# vending_machine_V1_0.net
KiCad netlist of a schematic drawn in Altium Designer
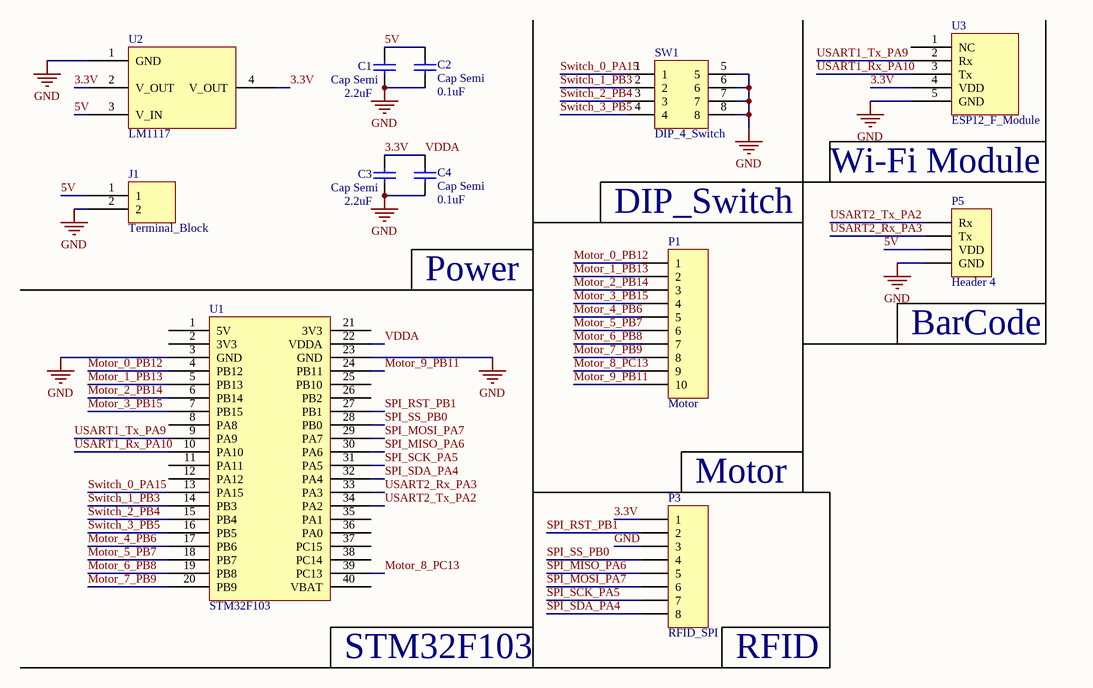
[diagram p0: vending_machine_V1.0.SchDoc]

(export (version "E")
  (design (tool "Eeschema 10.0.6"))
  (components
    (comp (ref "C1")
      (value "Cap Semi")
      (footprint "1608[0603]")
      (description "Capacitor (Semiconductor SIM Model)")
      (fields (field (name "ALTIUM_VALUE") "2.2uF") (field (name "PUBLISHER") "Altium Limited"))
      (libsource (lib "Miscellaneous Devices") (part "Cap Semi"))
    )
    (comp (ref "C2")
      (value "Cap Semi")
      (footprint "1608[0603]")
      (description "Capacitor (Semiconductor SIM Model)")
      (fields (field (name "ALTIUM_VALUE") "0.1uF") (field (name "PUBLISHER") "Altium Limited"))
      (libsource (lib "Miscellaneous Devices") (part "Cap Semi"))
    )
    (comp (ref "C3")
      (value "Cap Semi")
      (footprint "1608[0603]")
      (description "Capacitor (Semiconductor SIM Model)")
      (fields (field (name "ALTIUM_VALUE") "2.2uF") (field (name "PUBLISHER") "Altium Limited"))
      (libsource (lib "Miscellaneous Devices") (part "Cap Semi"))
    )
    (comp (ref "C4")
      (value "Cap Semi")
      (footprint "1608[0603]")
      (description "Capacitor (Semiconductor SIM Model)")
      (fields (field (name "ALTIUM_VALUE") "0.1uF") (field (name "PUBLISHER") "Altium Limited"))
      (libsource (lib "Miscellaneous Devices") (part "Cap Semi"))
    )
    (comp (ref "J1")
      (value "Terminal_Block")
      (footprint "terminal block")
      (libsource (lib "Lab_share") (part "Terminal Block"))
    )
    (comp (ref "P1")
      (value "Motor")
      (footprint "HDR1X10")
      (description "Header, 10-Pin")
      (fields (field (name "PUBLISHER") "Altium Limited"))
      (libsource (lib "Miscellaneous Connectors") (part "Header 10"))
    )
    (comp (ref "P3")
      (value "RFID_SPI")
      (footprint "HDR1X8")
      (description "Header, 8-Pin")
      (fields (field (name "PUBLISHER") "Altium Limited"))
      (libsource (lib "Miscellaneous Connectors") (part "Header 8"))
    )
    (comp (ref "P5")
      (value "Header 4")
      (footprint "HDR1X4")
      (description "Header, 4-Pin")
      (fields (field (name "PUBLISHER") "Altium Limited"))
      (libsource (lib "Miscellaneous Connectors") (part "Header 4"))
    )
    (comp (ref "SW1")
      (value "DIP_4_Switch")
      (footprint "Switch_4")
      (libsource (lib "Lab_share") (part "Switch_4"))
    )
    (comp (ref "U1")
      (value "STM32F103")
      (footprint "STM32F103")
      (libsource (lib "Lab_share") (part "STM32F103"))
    )
    (comp (ref "U2")
      (value "LM1117")
      (footprint "LM1117 - duplicate")
      (libsource (lib "Lab_share") (part "LM1117"))
    )
    (comp (ref "U3")
      (value "ESP12_F_Module")
      (footprint "ESP12_F_Holtek")
      (libsource (lib "Lab_share") (part "ESP12_F_Holtek"))
    )
  )
  (nets
    (net (code "1") (name "/3.3V") (class "Default")
      (node (ref "C3") (pin "2") (pinfunction "2_2") (pintype "passive"))
      (node (ref "C4") (pin "2") (pinfunction "2_2") (pintype "passive"))
      (node (ref "P3") (pin "1") (pinfunction "1_1") (pintype "passive"))
      (node (ref "U1") (pin "22") (pinfunction "VDDA_22") (pintype "passive"))
      (node (ref "U2") (pin "2") (pinfunction "V_OUT_2") (pintype "passive"))
      (node (ref "U2") (pin "4") (pinfunction "V_OUT_4") (pintype "passive"))
      (node (ref "U3") (pin "4") (pinfunction "VDD_4") (pintype "passive"))
    )
    (net (code "2") (name "/5V") (class "Default")
      (node (ref "C1") (pin "2") (pinfunction "2_2") (pintype "passive"))
      (node (ref "C2") (pin "2") (pinfunction "2_2") (pintype "passive"))
      (node (ref "J1") (pin "1") (pinfunction "1_1") (pintype "passive"))
      (node (ref "P5") (pin "3") (pinfunction "VDD_3") (pintype "passive"))
      (node (ref "U2") (pin "3") (pinfunction "V_IN_3") (pintype "passive"))
    )
    (net (code "3") (name "/Motor_0_PB12") (class "Default")
      (node (ref "P1") (pin "1") (pinfunction "1_1") (pintype "passive"))
      (node (ref "U1") (pin "4") (pinfunction "PB12_4") (pintype "passive"))
    )
    (net (code "4") (name "/Motor_1_PB13") (class "Default")
      (node (ref "P1") (pin "2") (pinfunction "2_2") (pintype "passive"))
      (node (ref "U1") (pin "5") (pinfunction "PB13_5") (pintype "passive"))
    )
    (net (code "5") (name "/Motor_2_PB14") (class "Default")
      (node (ref "P1") (pin "3") (pinfunction "3_3") (pintype "passive"))
      (node (ref "U1") (pin "6") (pinfunction "PB14_6") (pintype "passive"))
    )
    (net (code "6") (name "/Motor_3_PB15") (class "Default")
      (node (ref "P1") (pin "4") (pinfunction "4_4") (pintype "passive"))
      (node (ref "U1") (pin "7") (pinfunction "PB15_7") (pintype "passive"))
    )
    (net (code "7") (name "/Motor_4_PB6") (class "Default")
      (node (ref "P1") (pin "5") (pinfunction "5_5") (pintype "passive"))
      (node (ref "U1") (pin "17") (pinfunction "PB6_17") (pintype "passive"))
    )
    (net (code "8") (name "/Motor_5_PB7") (class "Default")
      (node (ref "P1") (pin "6") (pinfunction "6_6") (pintype "passive"))
      (node (ref "U1") (pin "18") (pinfunction "PB7_18") (pintype "passive"))
    )
    (net (code "9") (name "/Motor_6_PB8") (class "Default")
      (node (ref "P1") (pin "7") (pinfunction "7_7") (pintype "passive"))
      (node (ref "U1") (pin "19") (pinfunction "PB8_19") (pintype "passive"))
    )
    (net (code "10") (name "/Motor_7_PB9") (class "Default")
      (node (ref "P1") (pin "8") (pinfunction "8_8") (pintype "passive"))
      (node (ref "U1") (pin "20") (pinfunction "PB9_20") (pintype "passive"))
    )
    (net (code "11") (name "/Motor_8_PC13") (class "Default")
      (node (ref "P1") (pin "9") (pinfunction "9_9") (pintype "passive"))
      (node (ref "U1") (pin "39") (pinfunction "PC13_39") (pintype "passive"))
    )
    (net (code "12") (name "/Motor_9_PB11") (class "Default")
      (node (ref "P1") (pin "10") (pinfunction "10_10") (pintype "passive"))
      (node (ref "U1") (pin "24") (pinfunction "PB11_24") (pintype "passive"))
    )
    (net (code "13") (name "/SPI_MISO_PA6") (class "Default")
      (node (ref "P3") (pin "5") (pinfunction "5_5") (pintype "passive"))
      (node (ref "U1") (pin "30") (pinfunction "PA6_30") (pintype "passive"))
    )
    (net (code "14") (name "/SPI_MOSI_PA7") (class "Default")
      (node (ref "P3") (pin "6") (pinfunction "6_6") (pintype "passive"))
      (node (ref "U1") (pin "29") (pinfunction "PA7_29") (pintype "passive"))
    )
    (net (code "15") (name "/SPI_RST_PB1") (class "Default")
      (node (ref "P3") (pin "2") (pinfunction "2_2") (pintype "passive"))
      (node (ref "U1") (pin "27") (pinfunction "PB1_27") (pintype "passive"))
    )
    (net (code "16") (name "/SPI_SCK_PA5") (class "Default")
      (node (ref "P3") (pin "7") (pinfunction "7_7") (pintype "passive"))
      (node (ref "U1") (pin "31") (pinfunction "PA5_31") (pintype "passive"))
    )
    (net (code "17") (name "/SPI_SDA_PA4") (class "Default")
      (node (ref "P3") (pin "8") (pinfunction "8_8") (pintype "passive"))
      (node (ref "U1") (pin "32") (pinfunction "PA4_32") (pintype "passive"))
    )
    (net (code "18") (name "/SPI_SS_PB0") (class "Default")
      (node (ref "P3") (pin "4") (pinfunction "4_4") (pintype "passive"))
      (node (ref "U1") (pin "28") (pinfunction "PB0_28") (pintype "passive"))
    )
    (net (code "19") (name "/Switch_0_PA15") (class "Default")
      (node (ref "SW1") (pin "1") (pinfunction "1_1") (pintype "passive"))
      (node (ref "U1") (pin "13") (pinfunction "PA15_13") (pintype "passive"))
    )
    (net (code "20") (name "/Switch_1_PB3") (class "Default")
      (node (ref "SW1") (pin "2") (pinfunction "2_2") (pintype "passive"))
      (node (ref "U1") (pin "14") (pinfunction "PB3_14") (pintype "passive"))
    )
    (net (code "21") (name "/Switch_2_PB4") (class "Default")
      (node (ref "SW1") (pin "3") (pinfunction "3_3") (pintype "passive"))
      (node (ref "U1") (pin "15") (pinfunction "PB4_15") (pintype "passive"))
    )
    (net (code "22") (name "/Switch_3_PB5") (class "Default")
      (node (ref "SW1") (pin "4") (pinfunction "4_4") (pintype "passive"))
      (node (ref "U1") (pin "16") (pinfunction "PB5_16") (pintype "passive"))
    )
    (net (code "23") (name "/USART1_Rx_PA10") (class "Default")
      (node (ref "U1") (pin "10") (pinfunction "PA10_10") (pintype "passive"))
      (node (ref "U3") (pin "3") (pinfunction "Tx_3") (pintype "passive"))
    )
    (net (code "24") (name "/USART1_Tx_PA9") (class "Default")
      (node (ref "U1") (pin "9") (pinfunction "PA9_9") (pintype "passive"))
      (node (ref "U3") (pin "2") (pinfunction "Rx_2") (pintype "passive"))
    )
    (net (code "25") (name "/USART2_Rx_PA3") (class "Default")
      (node (ref "P5") (pin "2") (pinfunction "Tx_2") (pintype "passive"))
      (node (ref "U1") (pin "33") (pinfunction "PA3_33") (pintype "passive"))
    )
    (net (code "26") (name "/USART2_Tx_PA2") (class "Default")
      (node (ref "P5") (pin "1") (pinfunction "Rx_1") (pintype "passive"))
      (node (ref "U1") (pin "34") (pinfunction "PA2_34") (pintype "passive"))
    )
    (net (code "27") (name "GND") (class "Default")
      (node (ref "C1") (pin "1") (pinfunction "1_1") (pintype "passive"))
      (node (ref "C2") (pin "1") (pinfunction "1_1") (pintype "passive"))
      (node (ref "C3") (pin "1") (pinfunction "1_1") (pintype "passive"))
      (node (ref "C4") (pin "1") (pinfunction "1_1") (pintype "passive"))
      (node (ref "J1") (pin "2") (pinfunction "2_2") (pintype "passive"))
      (node (ref "P3") (pin "3") (pinfunction "3_3") (pintype "passive"))
      (node (ref "P5") (pin "4") (pinfunction "GND_4") (pintype "passive"))
      (node (ref "SW1") (pin "5") (pinfunction "5_5") (pintype "passive"))
      (node (ref "SW1") (pin "6") (pinfunction "6_6") (pintype "passive"))
      (node (ref "SW1") (pin "7") (pinfunction "7_7") (pintype "passive"))
      (node (ref "SW1") (pin "8") (pinfunction "8_8") (pintype "passive"))
      (node (ref "U1") (pin "23") (pinfunction "GND_23") (pintype "passive"))
      (node (ref "U1") (pin "3") (pinfunction "GND_3") (pintype "passive"))
      (node (ref "U2") (pin "1") (pinfunction "GND_1") (pintype "passive"))
      (node (ref "U3") (pin "5") (pinfunction "GND_5") (pintype "passive"))
    )
    (net (code "28") (name "unconnected-(U1-3V3-Pad2)") (class "Default")
      (node (ref "U1") (pin "2") (pinfunction "3V3_2") (pintype "passive"))
    )
    (net (code "29") (name "unconnected-(U1-3V3-Pad21)") (class "Default")
      (node (ref "U1") (pin "21") (pinfunction "3V3_21") (pintype "passive"))
    )
    (net (code "30") (name "unconnected-(U1-5V-Pad1)") (class "Default")
      (node (ref "U1") (pin "1") (pinfunction "5V_1") (pintype "passive"))
    )
    (net (code "31") (name "unconnected-(U1-PA0-Pad36)") (class "Default")
      (node (ref "U1") (pin "36") (pinfunction "PA0_36") (pintype "passive"))
    )
    (net (code "32") (name "unconnected-(U1-PA1-Pad35)") (class "Default")
      (node (ref "U1") (pin "35") (pinfunction "PA1_35") (pintype "passive"))
    )
    (net (code "33") (name "unconnected-(U1-PA8-Pad8)") (class "Default")
      (node (ref "U1") (pin "8") (pinfunction "PA8_8") (pintype "passive"))
    )
    (net (code "34") (name "unconnected-(U1-PA11-Pad11)") (class "Default")
      (node (ref "U1") (pin "11") (pinfunction "PA11_11") (pintype "passive"))
    )
    (net (code "35") (name "unconnected-(U1-PA12-Pad12)") (class "Default")
      (node (ref "U1") (pin "12") (pinfunction "PA12_12") (pintype "passive"))
    )
    (net (code "36") (name "unconnected-(U1-PB2-Pad26)") (class "Default")
      (node (ref "U1") (pin "26") (pinfunction "PB2_26") (pintype "passive"))
    )
    (net (code "37") (name "unconnected-(U1-PB10-Pad25)") (class "Default")
      (node (ref "U1") (pin "25") (pinfunction "PB10_25") (pintype "passive"))
    )
    (net (code "38") (name "unconnected-(U1-PC14-Pad38)") (class "Default")
      (node (ref "U1") (pin "38") (pinfunction "PC14_38") (pintype "passive"))
    )
    (net (code "39") (name "unconnected-(U1-PC15-Pad37)") (class "Default")
      (node (ref "U1") (pin "37") (pinfunction "PC15_37") (pintype "passive"))
    )
    (net (code "40") (name "unconnected-(U1-VBAT-Pad40)") (class "Default")
      (node (ref "U1") (pin "40") (pinfunction "VBAT_40") (pintype "passive"))
    )
    (net (code "41") (name "unconnected-(U3-NC-Pad1)") (class "Default")
      (node (ref "U3") (pin "1") (pinfunction "NC_1") (pintype "passive"))
    )
  )
)
